# CAN_Star.net
KiCad netlist of a schematic drawn in EAGLE
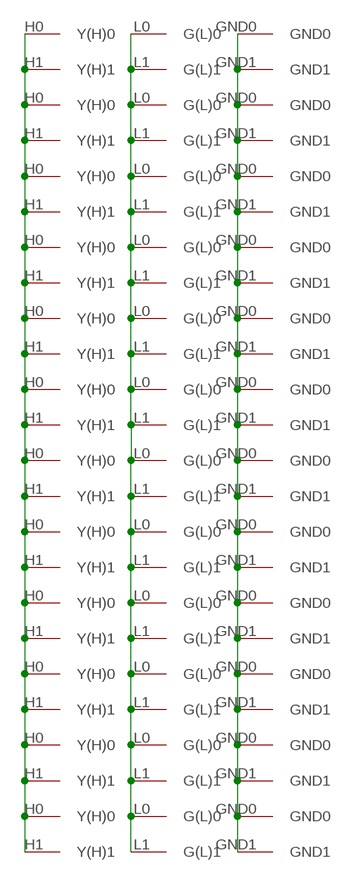
[diagram p0: schematic, sheet 1]

(export (version "E")
  (design (tool "Eeschema 10.0.6"))
  (components
    (comp (ref "U$1")
      (value "2-3-TERMS")
      (footprint "eagle-import:GREEN-2-TERMS")
      (libsource (lib "eagle-import") (part "2-3-TERMS"))
    )
    (comp (ref "U$2")
      (value "2-3-TERMS")
      (footprint "eagle-import:GREEN-2-TERMS")
      (libsource (lib "eagle-import") (part "2-3-TERMS"))
    )
    (comp (ref "U$3")
      (value "2-3-TERMS")
      (footprint "eagle-import:GREEN-2-TERMS")
      (libsource (lib "eagle-import") (part "2-3-TERMS"))
    )
    (comp (ref "U$4")
      (value "2-3-TERMS")
      (footprint "eagle-import:GREEN-2-TERMS")
      (libsource (lib "eagle-import") (part "2-3-TERMS"))
    )
    (comp (ref "U$5")
      (value "2-3-TERMS")
      (footprint "eagle-import:GREEN-2-TERMS")
      (libsource (lib "eagle-import") (part "2-3-TERMS"))
    )
    (comp (ref "U$6")
      (value "2-3-TERMS")
      (footprint "eagle-import:GREEN-2-TERMS")
      (libsource (lib "eagle-import") (part "2-3-TERMS"))
    )
    (comp (ref "U$7")
      (value "2-3-TERMS")
      (footprint "eagle-import:GREEN-2-TERMS")
      (libsource (lib "eagle-import") (part "2-3-TERMS"))
    )
    (comp (ref "U$8")
      (value "2-3-TERMS")
      (footprint "eagle-import:GREEN-2-TERMS")
      (libsource (lib "eagle-import") (part "2-3-TERMS"))
    )
    (comp (ref "U$9")
      (value "2-3-TERMS")
      (footprint "eagle-import:GREEN-2-TERMS")
      (libsource (lib "eagle-import") (part "2-3-TERMS"))
    )
    (comp (ref "U$10")
      (value "2-3-TERMS")
      (footprint "eagle-import:GREEN-2-TERMS")
      (libsource (lib "eagle-import") (part "2-3-TERMS"))
    )
    (comp (ref "U$11")
      (value "2-3-TERMS")
      (footprint "eagle-import:GREEN-2-TERMS")
      (libsource (lib "eagle-import") (part "2-3-TERMS"))
    )
    (comp (ref "U$12")
      (value "2-3-TERMS")
      (footprint "eagle-import:GREEN-2-TERMS")
      (libsource (lib "eagle-import") (part "2-3-TERMS"))
    )
  )
  (nets
    (net (code "1") (name "Net-(U$1-G(L)0)") (class "Default")
      (node (ref "U$1") (pin "L0") (pinfunction "G(L)0_L0") (pintype "bidirectional"))
      (node (ref "U$1") (pin "L1") (pinfunction "G(L)1_L1") (pintype "bidirectional"))
      (node (ref "U$10") (pin "L0") (pinfunction "G(L)0_L0") (pintype "bidirectional"))
      (node (ref "U$10") (pin "L1") (pinfunction "G(L)1_L1") (pintype "bidirectional"))
      (node (ref "U$11") (pin "L0") (pinfunction "G(L)0_L0") (pintype "bidirectional"))
      (node (ref "U$11") (pin "L1") (pinfunction "G(L)1_L1") (pintype "bidirectional"))
      (node (ref "U$12") (pin "L0") (pinfunction "G(L)0_L0") (pintype "bidirectional"))
      (node (ref "U$12") (pin "L1") (pinfunction "G(L)1_L1") (pintype "bidirectional"))
      (node (ref "U$2") (pin "L0") (pinfunction "G(L)0_L0") (pintype "bidirectional"))
      (node (ref "U$2") (pin "L1") (pinfunction "G(L)1_L1") (pintype "bidirectional"))
      (node (ref "U$3") (pin "L0") (pinfunction "G(L)0_L0") (pintype "bidirectional"))
      (node (ref "U$3") (pin "L1") (pinfunction "G(L)1_L1") (pintype "bidirectional"))
      (node (ref "U$4") (pin "L0") (pinfunction "G(L)0_L0") (pintype "bidirectional"))
      (node (ref "U$4") (pin "L1") (pinfunction "G(L)1_L1") (pintype "bidirectional"))
      (node (ref "U$5") (pin "L0") (pinfunction "G(L)0_L0") (pintype "bidirectional"))
      (node (ref "U$5") (pin "L1") (pinfunction "G(L)1_L1") (pintype "bidirectional"))
      (node (ref "U$6") (pin "L0") (pinfunction "G(L)0_L0") (pintype "bidirectional"))
      (node (ref "U$6") (pin "L1") (pinfunction "G(L)1_L1") (pintype "bidirectional"))
      (node (ref "U$7") (pin "L0") (pinfunction "G(L)0_L0") (pintype "bidirectional"))
      (node (ref "U$7") (pin "L1") (pinfunction "G(L)1_L1") (pintype "bidirectional"))
      (node (ref "U$8") (pin "L0") (pinfunction "G(L)0_L0") (pintype "bidirectional"))
      (node (ref "U$8") (pin "L1") (pinfunction "G(L)1_L1") (pintype "bidirectional"))
      (node (ref "U$9") (pin "L0") (pinfunction "G(L)0_L0") (pintype "bidirectional"))
      (node (ref "U$9") (pin "L1") (pinfunction "G(L)1_L1") (pintype "bidirectional"))
    )
    (net (code "2") (name "Net-(U$1-PadGND0)") (class "Default")
      (node (ref "U$1") (pin "GND0") (pinfunction "GND0_GND0") (pintype "bidirectional"))
      (node (ref "U$1") (pin "GND1") (pinfunction "GND1_GND1") (pintype "bidirectional"))
      (node (ref "U$10") (pin "GND0") (pinfunction "GND0_GND0") (pintype "bidirectional"))
      (node (ref "U$10") (pin "GND1") (pinfunction "GND1_GND1") (pintype "bidirectional"))
      (node (ref "U$11") (pin "GND0") (pinfunction "GND0_GND0") (pintype "bidirectional"))
      (node (ref "U$11") (pin "GND1") (pinfunction "GND1_GND1") (pintype "bidirectional"))
      (node (ref "U$12") (pin "GND0") (pinfunction "GND0_GND0") (pintype "bidirectional"))
      (node (ref "U$12") (pin "GND1") (pinfunction "GND1_GND1") (pintype "bidirectional"))
      (node (ref "U$2") (pin "GND0") (pinfunction "GND0_GND0") (pintype "bidirectional"))
      (node (ref "U$2") (pin "GND1") (pinfunction "GND1_GND1") (pintype "bidirectional"))
      (node (ref "U$3") (pin "GND0") (pinfunction "GND0_GND0") (pintype "bidirectional"))
      (node (ref "U$3") (pin "GND1") (pinfunction "GND1_GND1") (pintype "bidirectional"))
      (node (ref "U$4") (pin "GND0") (pinfunction "GND0_GND0") (pintype "bidirectional"))
      (node (ref "U$4") (pin "GND1") (pinfunction "GND1_GND1") (pintype "bidirectional"))
      (node (ref "U$5") (pin "GND0") (pinfunction "GND0_GND0") (pintype "bidirectional"))
      (node (ref "U$5") (pin "GND1") (pinfunction "GND1_GND1") (pintype "bidirectional"))
      (node (ref "U$6") (pin "GND0") (pinfunction "GND0_GND0") (pintype "bidirectional"))
      (node (ref "U$6") (pin "GND1") (pinfunction "GND1_GND1") (pintype "bidirectional"))
      (node (ref "U$7") (pin "GND0") (pinfunction "GND0_GND0") (pintype "bidirectional"))
      (node (ref "U$7") (pin "GND1") (pinfunction "GND1_GND1") (pintype "bidirectional"))
      (node (ref "U$8") (pin "GND0") (pinfunction "GND0_GND0") (pintype "bidirectional"))
      (node (ref "U$8") (pin "GND1") (pinfunction "GND1_GND1") (pintype "bidirectional"))
      (node (ref "U$9") (pin "GND0") (pinfunction "GND0_GND0") (pintype "bidirectional"))
      (node (ref "U$9") (pin "GND1") (pinfunction "GND1_GND1") (pintype "bidirectional"))
    )
    (net (code "3") (name "Net-(U$1-Y(H)0)") (class "Default")
      (node (ref "U$1") (pin "H0") (pinfunction "Y(H)0_H0") (pintype "bidirectional"))
      (node (ref "U$1") (pin "H1") (pinfunction "Y(H)1_H1") (pintype "bidirectional"))
      (node (ref "U$10") (pin "H0") (pinfunction "Y(H)0_H0") (pintype "bidirectional"))
      (node (ref "U$10") (pin "H1") (pinfunction "Y(H)1_H1") (pintype "bidirectional"))
      (node (ref "U$11") (pin "H0") (pinfunction "Y(H)0_H0") (pintype "bidirectional"))
      (node (ref "U$11") (pin "H1") (pinfunction "Y(H)1_H1") (pintype "bidirectional"))
      (node (ref "U$12") (pin "H0") (pinfunction "Y(H)0_H0") (pintype "bidirectional"))
      (node (ref "U$12") (pin "H1") (pinfunction "Y(H)1_H1") (pintype "bidirectional"))
      (node (ref "U$2") (pin "H0") (pinfunction "Y(H)0_H0") (pintype "bidirectional"))
      (node (ref "U$2") (pin "H1") (pinfunction "Y(H)1_H1") (pintype "bidirectional"))
      (node (ref "U$3") (pin "H0") (pinfunction "Y(H)0_H0") (pintype "bidirectional"))
      (node (ref "U$3") (pin "H1") (pinfunction "Y(H)1_H1") (pintype "bidirectional"))
      (node (ref "U$4") (pin "H0") (pinfunction "Y(H)0_H0") (pintype "bidirectional"))
      (node (ref "U$4") (pin "H1") (pinfunction "Y(H)1_H1") (pintype "bidirectional"))
      (node (ref "U$5") (pin "H0") (pinfunction "Y(H)0_H0") (pintype "bidirectional"))
      (node (ref "U$5") (pin "H1") (pinfunction "Y(H)1_H1") (pintype "bidirectional"))
      (node (ref "U$6") (pin "H0") (pinfunction "Y(H)0_H0") (pintype "bidirectional"))
      (node (ref "U$6") (pin "H1") (pinfunction "Y(H)1_H1") (pintype "bidirectional"))
      (node (ref "U$7") (pin "H0") (pinfunction "Y(H)0_H0") (pintype "bidirectional"))
      (node (ref "U$7") (pin "H1") (pinfunction "Y(H)1_H1") (pintype "bidirectional"))
      (node (ref "U$8") (pin "H0") (pinfunction "Y(H)0_H0") (pintype "bidirectional"))
      (node (ref "U$8") (pin "H1") (pinfunction "Y(H)1_H1") (pintype "bidirectional"))
      (node (ref "U$9") (pin "H0") (pinfunction "Y(H)0_H0") (pintype "bidirectional"))
      (node (ref "U$9") (pin "H1") (pinfunction "Y(H)1_H1") (pintype "bidirectional"))
    )
  )
)
